# XP_Driver.net
KiCad netlist of a schematic drawn in Altium Designer
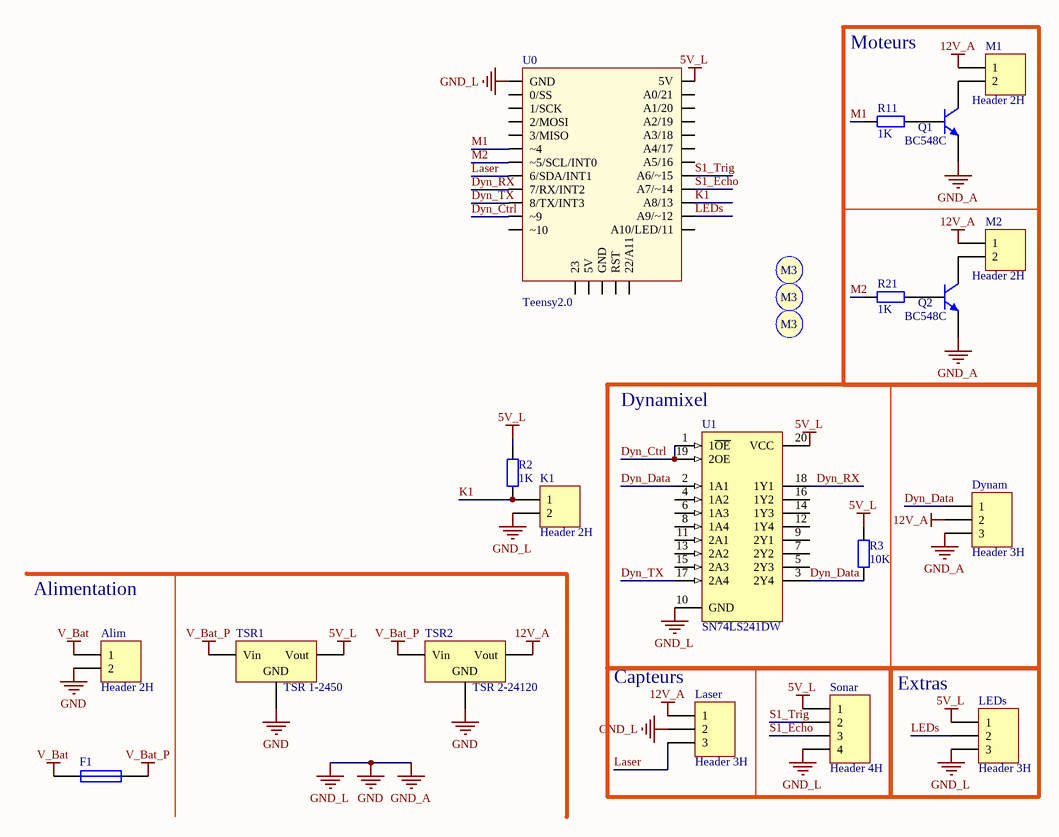
[diagram p0: XP_Driver.SchDoc]

(export (version "E")
  (design (tool "Eeschema 10.0.6"))
  (components
    (comp (ref "Alim")
      (value "Header 2H")
      (footprint "Molex_MiniFitJr_2x1H")
      (description "Header, 2-Pin, Right Angle")
      (fields (field (name "PUBLISHER") "Altium Limited"))
      (libsource (lib "Miscellaneous Connectors") (part "Header 2H"))
    )
    (comp (ref "Dynam")
      (value "Header 3H")
      (footprint "Molex SPOX 3x1H")
      (description "Header, 3-Pin, Right Angle")
      (fields (field (name "PUBLISHER") "Altium Limited"))
      (libsource (lib "Miscellaneous Connectors") (part "Header 3H"))
    )
    (comp (ref "F1")
      (value "Fuse 1")
      (footprint "Fuse")
      (description "Fuse")
      (fields (field (name "PUBLISHER") "Altium Limited"))
      (libsource (lib "Miscellaneous Devices") (part "Fuse 1"))
    )
    (comp (ref "K1")
      (value "Header 2H")
      (footprint "Molex SPOX 2x1H")
      (description "Header, 2-Pin, Right Angle")
      (fields (field (name "PUBLISHER") "Altium Limited"))
      (libsource (lib "Miscellaneous Connectors") (part "Header 2H"))
    )
    (comp (ref "Laser")
      (value "Header 3H")
      (footprint "MOLEX KK254 3X1H M")
      (description "Header, 3-Pin, Right Angle")
      (fields (field (name "PUBLISHER") "Altium Limited"))
      (libsource (lib "Miscellaneous Connectors") (part "Header 3H"))
    )
    (comp (ref "LEDs")
      (value "Header 3H")
      (footprint "Molex SPOX 3x1H")
      (description "Header, 3-Pin, Right Angle")
      (fields (field (name "PUBLISHER") "Altium Limited"))
      (libsource (lib "Miscellaneous Connectors") (part "Header 3H"))
    )
    (comp (ref "M1")
      (value "Header 2H")
      (footprint "Molex SPOX 2x1H")
      (description "Header, 2-Pin, Right Angle")
      (fields (field (name "PUBLISHER") "Altium Limited"))
      (libsource (lib "Miscellaneous Connectors") (part "Header 2H"))
    )
    (comp (ref "M2")
      (value "Header 2H")
      (footprint "Molex SPOX 2x1H")
      (description "Header, 2-Pin, Right Angle")
      (fields (field (name "PUBLISHER") "Altium Limited"))
      (libsource (lib "Miscellaneous Connectors") (part "Header 2H"))
    )
    (comp (ref "Q1")
      (value "BC548C")
      (footprint "TO-92A")
      (description "NPN General Purpose Amplifier")
      (fields (field (name "PUBLISHER") "Altium Limited"))
      (libsource (lib "Miscellaneous Devices") (part "2N3904"))
    )
    (comp (ref "Q2")
      (value "BC548C")
      (footprint "TO-92A")
      (description "NPN General Purpose Amplifier")
      (fields (field (name "PUBLISHER") "Altium Limited"))
      (libsource (lib "Miscellaneous Devices") (part "2N3904"))
    )
    (comp (ref "R2")
      (value "1K")
      (footprint "3.2X1.6X1.1")
      (description "Resistor")
      (fields (field (name "Comment") "Res2") (field (name "PUBLISHER") "Altium Limited"))
      (libsource (lib "Miscellaneous Devices") (part "Res2"))
    )
    (comp (ref "R3")
      (value "10K")
      (footprint "3.2X1.6X1.1")
      (description "Resistor")
      (fields (field (name "Comment") "Res2") (field (name "PUBLISHER") "Altium Limited"))
      (libsource (lib "") (part "Res2_1"))
    )
    (comp (ref "R11")
      (value "1K")
      (footprint "3.2X1.6X1.1")
      (description "Resistor")
      (fields (field (name "Comment") "Res2") (field (name "PUBLISHER") "Altium Limited"))
      (libsource (lib "") (part "Res2_2"))
    )
    (comp (ref "R21")
      (value "1K")
      (footprint "3.2X1.6X1.1")
      (description "Resistor")
      (fields (field (name "Comment") "Res2") (field (name "PUBLISHER") "Altium Limited"))
      (libsource (lib "") (part "Res2_2"))
    )
    (comp (ref "S1")
      (value "Screw M3")
      (footprint "Robot_2019:Screw M3")
      (libsource (lib "Robot_2019") (part "Screw M3"))
    )
    (comp (ref "S3")
      (value "Screw M3")
      (footprint "Robot_2019:Screw M3")
      (libsource (lib "Robot_2019") (part "Screw M3"))
    )
    (comp (ref "S4")
      (value "Screw M3")
      (footprint "Robot_2019:Screw M3")
      (libsource (lib "Robot_2019") (part "Screw M3"))
    )
    (comp (ref "Sonar")
      (value "Header 4H")
      (footprint "Molex SPOX 4x1H")
      (description "Header, 4-Pin, Right Angle")
      (fields (field (name "PUBLISHER") "Altium Limited"))
      (libsource (lib "Miscellaneous Connectors") (part "Header 4H"))
    )
    (comp (ref "TSR1")
      (value "TSR 1-2450")
      (footprint "TRS")
      (description "Voltage Regulator")
      (fields (field (name "PUBLISHER") "Altium Limited"))
      (libsource (lib "Miscellaneous Devices") (part "Volt Reg"))
    )
    (comp (ref "TSR2")
      (value "TSR 2-24120")
      (footprint "TRS - centered")
      (description "Voltage Regulator")
      (fields (field (name "PUBLISHER") "Altium Limited"))
      (libsource (lib "Miscellaneous Devices") (part "Volt Reg"))
    )
    (comp (ref "U0")
      (value "Teensy2.0")
      (footprint "Teensy2.0")
      (description "Teensy 2.0 with minimal pinout")
      (libsource (lib "Robot_2019") (part "Teensy2.0"))
    )
    (comp (ref "U1")
      (value "SN74LS241DW")
      (footprint "DW020_N")
      (description "Octal Buffer and Line Driver with 3-State Outputs")
      (fields (field (name "PUBLISHER") "Altium Limited"))
      (libsource (lib "TI Logic Buffer Line Driver") (part "SN74LS241DW"))
    )
  )
  (nets
    (net (code "1") (name "/Dyn_Ctrl") (class "Default")
      (node (ref "U0") (pin "11") (pinfunction "~9_11") (pintype "passive"))
      (node (ref "U1") (pin "1") (pinfunction "1~{OE}_1") (pintype "input"))
      (node (ref "U1") (pin "19") (pinfunction "2OE_19") (pintype "input"))
    )
    (net (code "2") (name "/Dyn_Data") (class "Default")
      (node (ref "Dynam") (pin "1") (pinfunction "1_1") (pintype "passive"))
      (node (ref "R3") (pin "1") (pinfunction "1_1") (pintype "passive"))
      (node (ref "U1") (pin "2") (pinfunction "1A1_2") (pintype "input"))
      (node (ref "U1") (pin "3") (pinfunction "2Y4_3") (pintype "tri_state"))
    )
    (net (code "3") (name "/Dyn_RX") (class "Default")
      (node (ref "U0") (pin "9") (pinfunction "7/RX/INT2_9") (pintype "passive"))
      (node (ref "U1") (pin "18") (pinfunction "1Y1_18") (pintype "tri_state"))
    )
    (net (code "4") (name "/Dyn_TX") (class "Default")
      (node (ref "U0") (pin "10") (pinfunction "8/TX/INT3_10") (pintype "passive"))
      (node (ref "U1") (pin "17") (pinfunction "2A4_17") (pintype "input"))
    )
    (net (code "5") (name "/K1") (class "Default")
      (node (ref "K1") (pin "1") (pinfunction "1_1") (pintype "passive"))
      (node (ref "R2") (pin "2") (pinfunction "2_2") (pintype "passive"))
      (node (ref "U0") (pin "20") (pinfunction "A8/13_20") (pintype "passive"))
    )
    (net (code "6") (name "/LEDs") (class "Default")
      (node (ref "LEDs") (pin "2") (pinfunction "2_2") (pintype "passive"))
      (node (ref "U0") (pin "19") (pinfunction "A9/~12_19") (pintype "passive"))
    )
    (net (code "7") (name "/Laser") (class "Default")
      (node (ref "Laser") (pin "3") (pinfunction "3_3") (pintype "passive"))
      (node (ref "U0") (pin "8") (pinfunction "6/SDA/INT1_8") (pintype "passive"))
    )
    (net (code "8") (name "/M1") (class "Default")
      (node (ref "R11") (pin "1") (pinfunction "1_1") (pintype "passive"))
      (node (ref "U0") (pin "6") (pinfunction "~4_6") (pintype "passive"))
    )
    (net (code "9") (name "/M2") (class "Default")
      (node (ref "R21") (pin "1") (pinfunction "1_1") (pintype "passive"))
      (node (ref "U0") (pin "7") (pinfunction "~5/SCL/INT0_7") (pintype "passive"))
    )
    (net (code "10") (name "/S1_Echo") (class "Default")
      (node (ref "Sonar") (pin "3") (pinfunction "3_3") (pintype "passive"))
      (node (ref "U0") (pin "21") (pinfunction "A7/~14_21") (pintype "passive"))
    )
    (net (code "11") (name "/S1_Trig") (class "Default")
      (node (ref "Sonar") (pin "2") (pinfunction "2_2") (pintype "passive"))
      (node (ref "U0") (pin "22") (pinfunction "A6/~15_22") (pintype "passive"))
    )
    (net (code "12") (name "5V_L") (class "Default")
      (node (ref "LEDs") (pin "1") (pinfunction "1_1") (pintype "passive"))
      (node (ref "R2") (pin "1") (pinfunction "1_1") (pintype "passive"))
      (node (ref "R3") (pin "2") (pinfunction "2_2") (pintype "passive"))
      (node (ref "Sonar") (pin "1") (pinfunction "1_1") (pintype "passive"))
      (node (ref "TSR1") (pin "3") (pinfunction "Vout_3") (pintype "passive"))
      (node (ref "U0") (pin "29") (pinfunction "5V_29") (pintype "passive"))
      (node (ref "U1") (pin "20") (pinfunction "VCC_20") (pintype "power_in"))
    )
    (net (code "13") (name "12V_A") (class "Default")
      (node (ref "Dynam") (pin "2") (pinfunction "2_2") (pintype "passive"))
      (node (ref "Laser") (pin "1") (pinfunction "1_1") (pintype "passive"))
      (node (ref "M1") (pin "1") (pinfunction "1_1") (pintype "passive"))
      (node (ref "M2") (pin "1") (pinfunction "1_1") (pintype "passive"))
      (node (ref "TSR2") (pin "3") (pinfunction "Vout_3") (pintype "passive"))
    )
    (net (code "14") (name "GND") (class "Default")
      (node (ref "Alim") (pin "2") (pinfunction "2_2") (pintype "passive"))
      (node (ref "Dynam") (pin "3") (pinfunction "3_3") (pintype "passive"))
      (node (ref "K1") (pin "2") (pinfunction "2_2") (pintype "passive"))
      (node (ref "LEDs") (pin "3") (pinfunction "3_3") (pintype "passive"))
      (node (ref "Laser") (pin "2") (pinfunction "2_2") (pintype "passive"))
      (node (ref "Q1") (pin "1") (pinfunction "E_1") (pintype "passive"))
      (node (ref "Q2") (pin "1") (pinfunction "E_1") (pintype "passive"))
      (node (ref "Sonar") (pin "4") (pinfunction "4_4") (pintype "passive"))
      (node (ref "TSR1") (pin "2") (pinfunction "GND_2") (pintype "passive"))
      (node (ref "TSR2") (pin "2") (pinfunction "GND_2") (pintype "passive"))
      (node (ref "U0") (pin "1") (pinfunction "GND_1") (pintype "passive"))
      (node (ref "U1") (pin "10") (pinfunction "GND_10") (pintype "power_in"))
    )
    (net (code "15") (name "Net-(Q1-B)") (class "Default")
      (node (ref "Q1") (pin "2") (pinfunction "B_2") (pintype "passive"))
      (node (ref "R11") (pin "2") (pinfunction "2_2") (pintype "passive"))
    )
    (net (code "16") (name "Net-(Q1-C)") (class "Default")
      (node (ref "M1") (pin "2") (pinfunction "2_2") (pintype "passive"))
      (node (ref "Q1") (pin "3") (pinfunction "C_3") (pintype "passive"))
    )
    (net (code "17") (name "Net-(Q2-B)") (class "Default")
      (node (ref "Q2") (pin "2") (pinfunction "B_2") (pintype "passive"))
      (node (ref "R21") (pin "2") (pinfunction "2_2") (pintype "passive"))
    )
    (net (code "18") (name "Net-(Q2-C)") (class "Default")
      (node (ref "M2") (pin "2") (pinfunction "2_2") (pintype "passive"))
      (node (ref "Q2") (pin "3") (pinfunction "C_3") (pintype "passive"))
    )
    (net (code "19") (name "V_Bat") (class "Default")
      (node (ref "Alim") (pin "1") (pinfunction "1_1") (pintype "passive"))
      (node (ref "F1") (pin "1") (pinfunction "1_1") (pintype "passive"))
    )
    (net (code "20") (name "V_Bat_P") (class "Default")
      (node (ref "F1") (pin "2") (pinfunction "2_2") (pintype "passive"))
      (node (ref "TSR1") (pin "1") (pinfunction "Vin_1") (pintype "passive"))
      (node (ref "TSR2") (pin "1") (pinfunction "Vin_1") (pintype "passive"))
    )
    (net (code "21") (name "unconnected-(U0-0{slash}SS-Pad2)") (class "Default")
      (node (ref "U0") (pin "2") (pinfunction "0/SS_2") (pintype "passive"))
    )
    (net (code "22") (name "unconnected-(U0-1{slash}SCK-Pad3)") (class "Default")
      (node (ref "U0") (pin "3") (pinfunction "1/SCK_3") (pintype "passive"))
    )
    (net (code "23") (name "unconnected-(U0-2{slash}MOSI-Pad4)") (class "Default")
      (node (ref "U0") (pin "4") (pinfunction "2/MOSI_4") (pintype "passive"))
    )
    (net (code "24") (name "unconnected-(U0-3{slash}MISO-Pad5)") (class "Default")
      (node (ref "U0") (pin "5") (pinfunction "3/MISO_5") (pintype "passive"))
    )
    (net (code "25") (name "unconnected-(U0-5V-Pad14)") (class "Default")
      (node (ref "U0") (pin "14") (pinfunction "5V_14") (pintype "passive"))
    )
    (net (code "26") (name "unconnected-(U0-22{slash}A11-Pad17)") (class "Default")
      (node (ref "U0") (pin "17") (pinfunction "22/A11_17") (pintype "passive"))
    )
    (net (code "27") (name "unconnected-(U0-23-Pad13)") (class "Default")
      (node (ref "U0") (pin "13") (pinfunction "23_13") (pintype "passive"))
    )
    (net (code "28") (name "unconnected-(U0-A0{slash}21-Pad28)") (class "Default")
      (node (ref "U0") (pin "28") (pinfunction "A0/21_28") (pintype "passive"))
    )
    (net (code "29") (name "unconnected-(U0-A1{slash}20-Pad27)") (class "Default")
      (node (ref "U0") (pin "27") (pinfunction "A1/20_27") (pintype "passive"))
    )
    (net (code "30") (name "unconnected-(U0-A2{slash}19-Pad26)") (class "Default")
      (node (ref "U0") (pin "26") (pinfunction "A2/19_26") (pintype "passive"))
    )
    (net (code "31") (name "unconnected-(U0-A3{slash}18-Pad25)") (class "Default")
      (node (ref "U0") (pin "25") (pinfunction "A3/18_25") (pintype "passive"))
    )
    (net (code "32") (name "unconnected-(U0-A4{slash}17-Pad24)") (class "Default")
      (node (ref "U0") (pin "24") (pinfunction "A4/17_24") (pintype "passive"))
    )
    (net (code "33") (name "unconnected-(U0-A5{slash}16-Pad23)") (class "Default")
      (node (ref "U0") (pin "23") (pinfunction "A5/16_23") (pintype "passive"))
    )
    (net (code "34") (name "unconnected-(U0-A10{slash}LED{slash}11-Pad18)") (class "Default")
      (node (ref "U0") (pin "18") (pinfunction "A10/LED/11_18") (pintype "passive"))
    )
    (net (code "35") (name "unconnected-(U0-GND-Pad15)") (class "Default")
      (node (ref "U0") (pin "15") (pinfunction "GND_15") (pintype "passive"))
    )
    (net (code "36") (name "unconnected-(U0-RST-Pad16)") (class "Default")
      (node (ref "U0") (pin "16") (pinfunction "RST_16") (pintype "passive"))
    )
    (net (code "37") (name "unconnected-(U0-~10-Pad12)") (class "Default")
      (node (ref "U0") (pin "12") (pinfunction "~10_12") (pintype "passive"))
    )
    (net (code "38") (name "unconnected-(U1-1A2-Pad4)") (class "Default")
      (node (ref "U1") (pin "4") (pinfunction "1A2_4") (pintype "input"))
    )
    (net (code "39") (name "unconnected-(U1-1A3-Pad6)") (class "Default")
      (node (ref "U1") (pin "6") (pinfunction "1A3_6") (pintype "input"))
    )
    (net (code "40") (name "unconnected-(U1-1A4-Pad8)") (class "Default")
      (node (ref "U1") (pin "8") (pinfunction "1A4_8") (pintype "input"))
    )
    (net (code "41") (name "unconnected-(U1-1Y2-Pad16)") (class "Default")
      (node (ref "U1") (pin "16") (pinfunction "1Y2_16") (pintype "tri_state"))
    )
    (net (code "42") (name "unconnected-(U1-1Y3-Pad14)") (class "Default")
      (node (ref "U1") (pin "14") (pinfunction "1Y3_14") (pintype "tri_state"))
    )
    (net (code "43") (name "unconnected-(U1-1Y4-Pad12)") (class "Default")
      (node (ref "U1") (pin "12") (pinfunction "1Y4_12") (pintype "tri_state"))
    )
    (net (code "44") (name "unconnected-(U1-2A1-Pad11)") (class "Default")
      (node (ref "U1") (pin "11") (pinfunction "2A1_11") (pintype "input"))
    )
    (net (code "45") (name "unconnected-(U1-2A2-Pad13)") (class "Default")
      (node (ref "U1") (pin "13") (pinfunction "2A2_13") (pintype "input"))
    )
    (net (code "46") (name "unconnected-(U1-2A3-Pad15)") (class "Default")
      (node (ref "U1") (pin "15") (pinfunction "2A3_15") (pintype "input"))
    )
    (net (code "47") (name "unconnected-(U1-2Y1-Pad9)") (class "Default")
      (node (ref "U1") (pin "9") (pinfunction "2Y1_9") (pintype "tri_state"))
    )
    (net (code "48") (name "unconnected-(U1-2Y2-Pad7)") (class "Default")
      (node (ref "U1") (pin "7") (pinfunction "2Y2_7") (pintype "tri_state"))
    )
    (net (code "49") (name "unconnected-(U1-2Y3-Pad5)") (class "Default")
      (node (ref "U1") (pin "5") (pinfunction "2Y3_5") (pintype "tri_state"))
    )
  )
)
